# MISC.net
KiCad netlist of a schematic drawn in Altium Designer
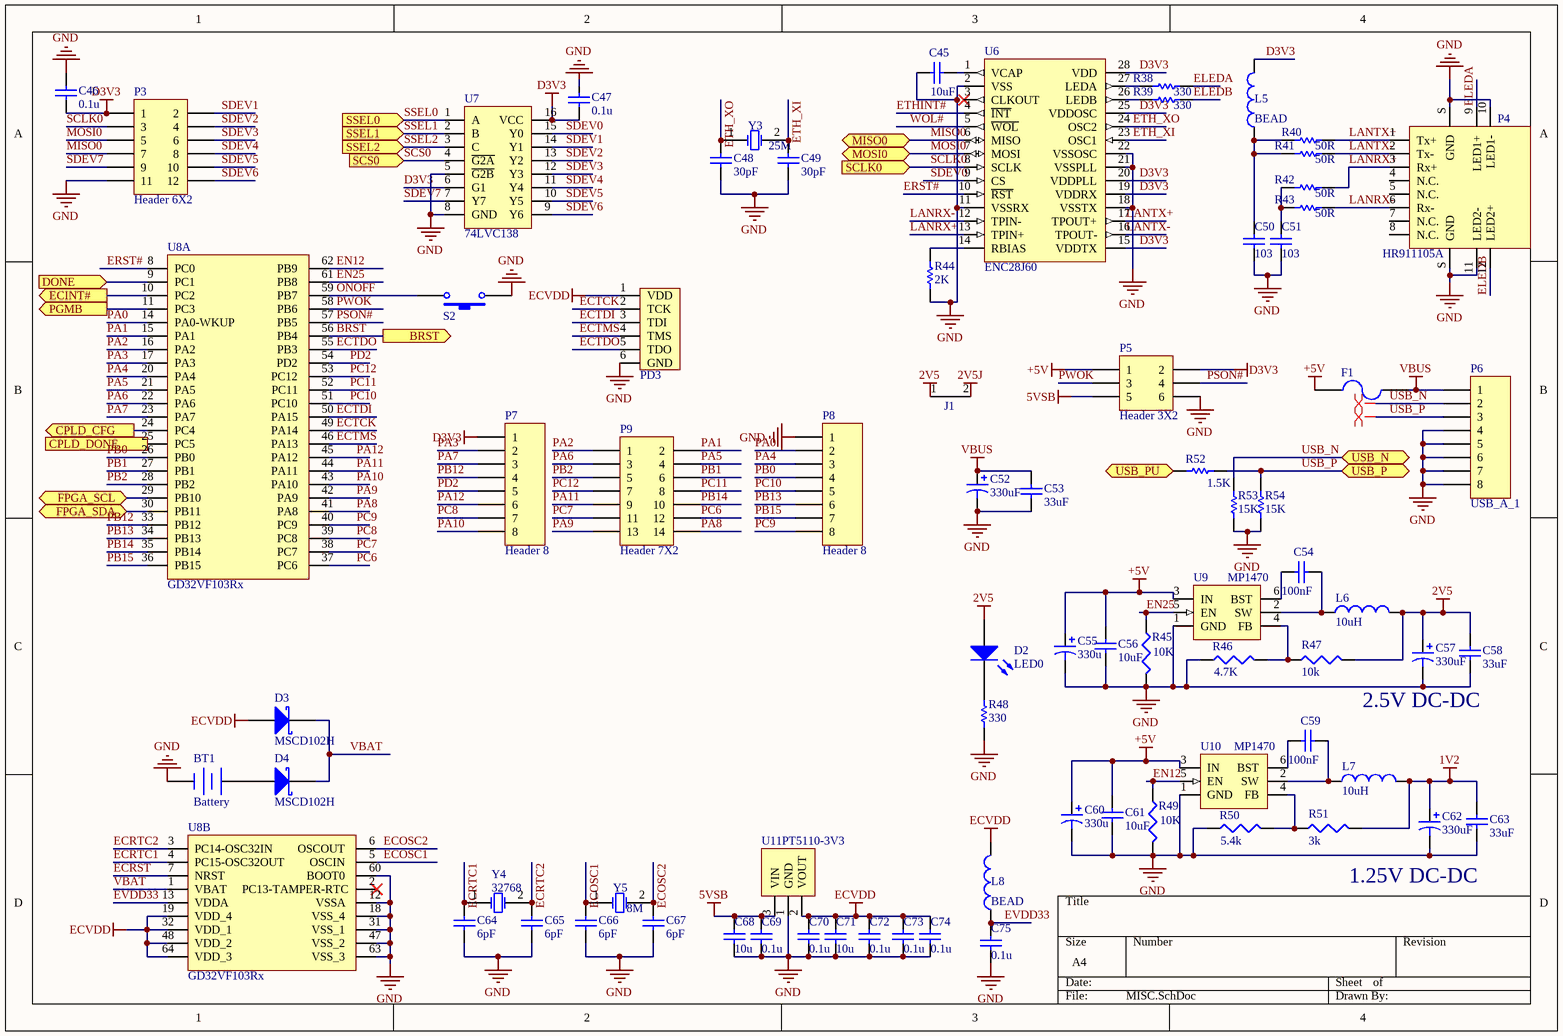
[diagram p0: MISC.SchDoc]

(export (version "E")
  (design (tool "Eeschema 10.0.6"))
  (components
    (comp (ref "BT1")
      (value "Battery")
      (footprint "BAT-CR1220")
      (description "Multicell Battery")
      (fields (field (name "PUBLISHER") "Altium Limited"))
      (libsource (lib "Miscellaneous Devices") (part "Battery"))
    )
    (comp (ref "C45")
      (value "10uF")
      (footprint "0603C")
      (description "Capacitor")
      (fields (field (name "Comment") "Cap") (field (name "PUBLISHER") "Altium Limited"))
      (libsource (lib "Miscellaneous Devices") (part "Cap"))
    )
    (comp (ref "C46")
      (value "0.1u")
      (footprint "0603C")
      (description "Capacitor")
      (fields (field (name "Comment") "Cap") (field (name "PUBLISHER") "Altium Limited"))
      (libsource (lib "Miscellaneous Devices") (part "Cap"))
    )
    (comp (ref "C47")
      (value "0.1u")
      (footprint "0603C")
      (description "Capacitor")
      (fields (field (name "Comment") "Cap") (field (name "PUBLISHER") "Altium Limited"))
      (libsource (lib "Miscellaneous Devices") (part "Cap"))
    )
    (comp (ref "C48")
      (value "30pF")
      (footprint "0603C")
      (description "Capacitor")
      (fields (field (name "Comment") "Cap") (field (name "PUBLISHER") "Altium Limited"))
      (libsource (lib "Miscellaneous Devices") (part "Cap"))
    )
    (comp (ref "C49")
      (value "30pF")
      (footprint "0603C")
      (description "Capacitor")
      (fields (field (name "Comment") "Cap") (field (name "PUBLISHER") "Altium Limited"))
      (libsource (lib "Miscellaneous Devices") (part "Cap"))
    )
    (comp (ref "C50")
      (value "103")
      (footprint "0603C")
      (description "Capacitor")
      (fields (field (name "Comment") "Cap") (field (name "PUBLISHER") "Altium Limited"))
      (libsource (lib "Miscellaneous Devices") (part "Cap"))
    )
    (comp (ref "C51")
      (value "103")
      (footprint "0603C")
      (description "Capacitor")
      (fields (field (name "Comment") "Cap") (field (name "PUBLISHER") "Altium Limited"))
      (libsource (lib "Miscellaneous Devices") (part "Cap"))
    )
    (comp (ref "C52")
      (value "330uF")
      (footprint "TanCap-1210")
      (description "Polarized Capacitor (Radial)")
      (fields (field (name "Comment") "330u") (field (name "PUBLISHER") "Altium Limited"))
      (libsource (lib "Miscellaneous Devices") (part "Cap Pol1"))
    )
    (comp (ref "C53")
      (value "33uF")
      (footprint "0603C")
      (description "Ceramic Capacitor 0603")
      (fields (field (name "Comment") "106") (field (name "PUBLISHER") "Altium Limited"))
      (libsource (lib "Miscellaneous Devices") (part "Cap"))
    )
    (comp (ref "C54")
      (value "100nF")
      (footprint "0603C")
      (description "Ceramic Capacitor 0603")
      (fields (field (name "Comment") "104") (field (name "PUBLISHER") "Altium Limited"))
      (libsource (lib "Miscellaneous Devices") (part "Cap"))
    )
    (comp (ref "C55")
      (value "330u")
      (footprint "TanCap-1210")
      (description "Polarized Capacitor (Radial)")
      (fields (field (name "PUBLISHER") "Altium Limited"))
      (libsource (lib "Miscellaneous Devices") (part "Cap Pol1"))
    )
    (comp (ref "C56")
      (value "10uF")
      (footprint "0603C")
      (description "Ceramic Capacitor 0603")
      (fields (field (name "Comment") "106") (field (name "PUBLISHER") "Altium Limited"))
      (libsource (lib "Miscellaneous Devices") (part "Cap"))
    )
    (comp (ref "C57")
      (value "330uF")
      (footprint "TanCap-1210")
      (description "Polarized Capacitor (Radial)")
      (fields (field (name "Comment") "330u") (field (name "PUBLISHER") "Altium Limited"))
      (libsource (lib "Miscellaneous Devices") (part "Cap Pol1"))
    )
    (comp (ref "C58")
      (value "33uF")
      (footprint "0603C")
      (description "Ceramic Capacitor 0603")
      (fields (field (name "Comment") "106") (field (name "PUBLISHER") "Altium Limited"))
      (libsource (lib "Miscellaneous Devices") (part "Cap"))
    )
    (comp (ref "C59")
      (value "100nF")
      (footprint "0603C")
      (description "Ceramic Capacitor 0603")
      (fields (field (name "Comment") "104") (field (name "PUBLISHER") "Altium Limited"))
      (libsource (lib "Miscellaneous Devices") (part "Cap"))
    )
    (comp (ref "C60")
      (value "330u")
      (footprint "TanCap-1210")
      (description "Polarized Capacitor (Radial)")
      (fields (field (name "PUBLISHER") "Altium Limited"))
      (libsource (lib "Miscellaneous Devices") (part "Cap Pol1"))
    )
    (comp (ref "C61")
      (value "10uF")
      (footprint "0603C")
      (description "Ceramic Capacitor 0603")
      (fields (field (name "Comment") "106") (field (name "PUBLISHER") "Altium Limited"))
      (libsource (lib "Miscellaneous Devices") (part "Cap"))
    )
    (comp (ref "C62")
      (value "330uF")
      (footprint "TanCap-1210")
      (description "Polarized Capacitor (Radial)")
      (fields (field (name "Comment") "330u") (field (name "PUBLISHER") "Altium Limited"))
      (libsource (lib "Miscellaneous Devices") (part "Cap Pol1"))
    )
    (comp (ref "C63")
      (value "33uF")
      (footprint "0603C")
      (description "Ceramic Capacitor 0603")
      (fields (field (name "Comment") "106") (field (name "PUBLISHER") "Altium Limited"))
      (libsource (lib "Miscellaneous Devices") (part "Cap"))
    )
    (comp (ref "C64")
      (value "6pF")
      (footprint "0603C")
      (description "Capacitor")
      (fields (field (name "Comment") "Cap") (field (name "PUBLISHER") "Altium Limited"))
      (libsource (lib "Miscellaneous Devices") (part "Cap"))
    )
    (comp (ref "C65")
      (value "6pF")
      (footprint "0603C")
      (description "Capacitor")
      (fields (field (name "Comment") "Cap") (field (name "PUBLISHER") "Altium Limited"))
      (libsource (lib "Miscellaneous Devices") (part "Cap"))
    )
    (comp (ref "C66")
      (value "6pF")
      (footprint "0603C")
      (description "Capacitor")
      (fields (field (name "Comment") "Cap") (field (name "PUBLISHER") "Altium Limited"))
      (libsource (lib "Miscellaneous Devices") (part "Cap"))
    )
    (comp (ref "C67")
      (value "6pF")
      (footprint "0603C")
      (description "Capacitor")
      (fields (field (name "Comment") "Cap") (field (name "PUBLISHER") "Altium Limited"))
      (libsource (lib "Miscellaneous Devices") (part "Cap"))
    )
    (comp (ref "C68")
      (value "10u")
      (footprint "0603C")
      (description "Capacitor")
      (fields (field (name "Comment") "Cap") (field (name "PUBLISHER") "Altium Limited"))
      (libsource (lib "Miscellaneous Devices") (part "Cap"))
    )
    (comp (ref "C69")
      (value "0.1u")
      (footprint "0603C")
      (description "Capacitor")
      (fields (field (name "Comment") "Cap") (field (name "PUBLISHER") "Altium Limited"))
      (libsource (lib "Miscellaneous Devices") (part "Cap"))
    )
    (comp (ref "C70")
      (value "0.1u")
      (footprint "0603C")
      (description "Capacitor")
      (fields (field (name "Comment") "Cap") (field (name "PUBLISHER") "Altium Limited"))
      (libsource (lib "Miscellaneous Devices") (part "Cap"))
    )
    (comp (ref "C71")
      (value "10u")
      (footprint "0603C")
      (description "Capacitor")
      (fields (field (name "Comment") "Cap") (field (name "PUBLISHER") "Altium Limited"))
      (libsource (lib "Miscellaneous Devices") (part "Cap"))
    )
    (comp (ref "C72")
      (value "0.1u")
      (footprint "0603C")
      (description "Capacitor")
      (fields (field (name "Comment") "Cap") (field (name "PUBLISHER") "Altium Limited"))
      (libsource (lib "Miscellaneous Devices") (part "Cap"))
    )
    (comp (ref "C73")
      (value "0.1u")
      (footprint "0603C")
      (description "Capacitor")
      (fields (field (name "Comment") "Cap") (field (name "PUBLISHER") "Altium Limited"))
      (libsource (lib "Miscellaneous Devices") (part "Cap"))
    )
    (comp (ref "C74")
      (value "0.1u")
      (footprint "0603C")
      (description "Capacitor")
      (fields (field (name "Comment") "Cap") (field (name "PUBLISHER") "Altium Limited"))
      (libsource (lib "Miscellaneous Devices") (part "Cap"))
    )
    (comp (ref "C75")
      (value "0.1u")
      (footprint "0603C")
      (description "Capacitor")
      (fields (field (name "Comment") "Cap") (field (name "PUBLISHER") "Altium Limited"))
      (libsource (lib "Miscellaneous Devices") (part "Cap"))
    )
    (comp (ref "D2")
      (value "LED0")
      (footprint "0805LED1")
      (description "Typical INFRARED GaAs LED")
      (fields (field (name "PUBLISHER") "Altium Limited"))
      (libsource (lib "Miscellaneous Devices") (part "LED0"))
    )
    (comp (ref "D3")
      (value "MSCD102H")
      (footprint "0805LED2")
      (description "Schottky Diode")
      (fields (field (name "PUBLISHER") "Altium Limited"))
      (libsource (lib "Miscellaneous Devices") (part "D Schottky"))
    )
    (comp (ref "D4")
      (value "MSCD102H")
      (footprint "0805LED2")
      (description "Schottky Diode")
      (fields (field (name "PUBLISHER") "Altium Limited"))
      (libsource (lib "Miscellaneous Devices") (part "D Schottky"))
    )
    (comp (ref "F1")
      (value "Fuse 2")
      (footprint "Fusebux_5x20")
      (description "Fuse")
      (fields (field (name "PUBLISHER") "Altium Limited"))
      (libsource (lib "Miscellaneous Devices") (part "Fuse 2"))
    )
    (comp (ref "J1")
      (value "Jumper")
      (footprint "Jumper 10mm")
      (libsource (lib "RV_AT_Ports") (part "Jumper"))
    )
    (comp (ref "L5")
      (value "BEAD")
      (footprint "0603C")
      (description "Inductor")
      (fields (field (name "PUBLISHER") "Altium Limited"))
      (libsource (lib "Miscellaneous Devices") (part "Inductor"))
    )
    (comp (ref "L6")
      (value "10uH")
      (footprint "PIND0650")
      (description "Inductor 0606")
      (fields (field (name "PUBLISHER") "Altium Limited"))
      (libsource (lib "Miscellaneous Devices") (part "Inductor"))
    )
    (comp (ref "L7")
      (value "10uH")
      (footprint "PIND0650")
      (description "Inductor 0606")
      (fields (field (name "PUBLISHER") "Altium Limited"))
      (libsource (lib "Miscellaneous Devices") (part "Inductor"))
    )
    (comp (ref "L8")
      (value "BEAD")
      (footprint "0603C")
      (description "Inductor")
      (fields (field (name "PUBLISHER") "Altium Limited"))
      (libsource (lib "Miscellaneous Devices") (part "Inductor"))
    )
    (comp (ref "P3")
      (value "Header 6X2")
      (footprint "HDR2X6")
      (description "Header, 6-Pin, Dual row")
      (fields (field (name "PUBLISHER") "Altium Limited"))
      (libsource (lib "Miscellaneous Connectors") (part "Header 6X2"))
    )
    (comp (ref "P4")
      (value "HR911105A")
      (footprint "HR911105A")
      (libsource (lib "ETH_Solution") (part "HR911105A"))
    )
    (comp (ref "P5")
      (value "Header 3X2")
      (footprint "PWRCONN-6P")
      (description "Header, 3-Pin, Dual row")
      (fields (field (name "PUBLISHER") "Altium Limited"))
      (libsource (lib "Miscellaneous Connectors") (part "Header 3X2"))
    )
    (comp (ref "P6")
      (value "USB_A_1")
      (footprint "USB-A_1")
      (description "Header, 8-Pin")
      (fields (field (name "PUBLISHER") "Altium Limited"))
      (libsource (lib "Miscellaneous Connectors") (part "Header 8"))
    )
    (comp (ref "P7")
      (value "Header 8")
      (footprint "HDR1X8")
      (description "Header, 8-Pin")
      (fields (field (name "PUBLISHER") "Altium Limited"))
      (libsource (lib "Miscellaneous Connectors") (part "Header 8"))
    )
    (comp (ref "P8")
      (value "Header 8")
      (footprint "HDR1X8")
      (description "Header, 8-Pin")
      (fields (field (name "PUBLISHER") "Altium Limited"))
      (libsource (lib "Miscellaneous Connectors") (part "Header 8"))
    )
    (comp (ref "P9")
      (value "Header 7X2")
      (footprint "HDR2X7_U")
      (description "Header, 7-Pin, Dual row")
      (fields (field (name "PUBLISHER") "Altium Limited"))
      (libsource (lib "Miscellaneous Connectors") (part "Header 7X2"))
    )
    (comp (ref "PD3") (value "JTAG") (footprint "DBGP7") (libsource (lib "RV_AT_Ports") (part "JTAG")))
    (comp (ref "R38")
      (value "330")
      (footprint "0603R")
      (description "Resistor")
      (fields (field (name "Comment") "Res1") (field (name "PUBLISHER") "Altium Limited"))
      (libsource (lib "Miscellaneous Devices") (part "Res1"))
    )
    (comp (ref "R39")
      (value "330")
      (footprint "0603R")
      (description "Resistor")
      (fields (field (name "Comment") "Res1") (field (name "PUBLISHER") "Altium Limited"))
      (libsource (lib "Miscellaneous Devices") (part "Res1"))
    )
    (comp (ref "R40")
      (value "50R")
      (footprint "0603R")
      (description "Resistor")
      (fields (field (name "Comment") "Res1") (field (name "PUBLISHER") "Altium Limited"))
      (libsource (lib "Miscellaneous Devices") (part "Res1"))
    )
    (comp (ref "R41")
      (value "50R")
      (footprint "0603R")
      (description "Resistor")
      (fields (field (name "Comment") "Res1") (field (name "PUBLISHER") "Altium Limited"))
      (libsource (lib "Miscellaneous Devices") (part "Res1"))
    )
    (comp (ref "R42")
      (value "50R")
      (footprint "0603R")
      (description "Resistor")
      (fields (field (name "Comment") "Res1") (field (name "PUBLISHER") "Altium Limited"))
      (libsource (lib "Miscellaneous Devices") (part "Res1"))
    )
    (comp (ref "R43")
      (value "50R")
      (footprint "0603R")
      (description "Resistor")
      (fields (field (name "Comment") "Res1") (field (name "PUBLISHER") "Altium Limited"))
      (libsource (lib "Miscellaneous Devices") (part "Res1"))
    )
    (comp (ref "R44")
      (value "2K")
      (footprint "0603R")
      (description "Resistor")
      (fields (field (name "Comment") "Res1") (field (name "PUBLISHER") "Altium Limited"))
      (libsource (lib "Miscellaneous Devices") (part "Res1"))
    )
    (comp (ref "R45")
      (value "10K")
      (footprint "0603R")
      (description "Resistor")
      (fields (field (name "PUBLISHER") "Altium Limited"))
      (libsource (lib "Miscellaneous Devices") (part "Res3"))
    )
    (comp (ref "R46")
      (value "4.7K")
      (footprint "0603R")
      (description "Resistor")
      (fields (field (name "Comment") "3K2") (field (name "PUBLISHER") "Altium Limited"))
      (libsource (lib "Miscellaneous Devices") (part "Res3"))
    )
    (comp (ref "R47")
      (value "10k")
      (footprint "0603R")
      (description "Resistor")
      (fields (field (name "Comment") "10K") (field (name "PUBLISHER") "Altium Limited"))
      (libsource (lib "Miscellaneous Devices") (part "Res3"))
    )
    (comp (ref "R48")
      (value "330")
      (footprint "0603R")
      (description "Resistor")
      (fields (field (name "Comment") "Res1") (field (name "PUBLISHER") "Altium Limited"))
      (libsource (lib "Miscellaneous Devices") (part "Res1"))
    )
    (comp (ref "R49")
      (value "10K")
      (footprint "0603R")
      (description "Resistor")
      (fields (field (name "PUBLISHER") "Altium Limited"))
      (libsource (lib "Miscellaneous Devices") (part "Res3"))
    )
    (comp (ref "R50")
      (value "5.4k")
      (footprint "0603R")
      (description "Resistor")
      (fields (field (name "Comment") "3K2") (field (name "PUBLISHER") "Altium Limited"))
      (libsource (lib "Miscellaneous Devices") (part "Res3"))
    )
    (comp (ref "R51")
      (value "3k")
      (footprint "0603R")
      (description "Resistor")
      (fields (field (name "Comment") "10K") (field (name "PUBLISHER") "Altium Limited"))
      (libsource (lib "Miscellaneous Devices") (part "Res3"))
    )
    (comp (ref "R52")
      (value "1.5K")
      (footprint "0603R")
      (description "Resistor")
      (fields (field (name "Comment") "Res1") (field (name "PUBLISHER") "Altium Limited"))
      (libsource (lib "Miscellaneous Devices") (part "Res1"))
    )
    (comp (ref "R53")
      (value "15K")
      (footprint "0603R")
      (description "Resistor")
      (fields (field (name "Comment") "Res1") (field (name "PUBLISHER") "Altium Limited"))
      (libsource (lib "Miscellaneous Devices") (part "Res1"))
    )
    (comp (ref "R54")
      (value "15K")
      (footprint "0603R")
      (description "Resistor")
      (fields (field (name "Comment") "Res1") (field (name "PUBLISHER") "Altium Limited"))
      (libsource (lib "Miscellaneous Devices") (part "Res1"))
    )
    (comp (ref "S2")
      (value "SW-PB")
      (footprint "Switch_SMT-022S-H2.5")
      (description "Switch")
      (fields (field (name "PUBLISHER") "Altium Limited"))
      (libsource (lib "Miscellaneous Devices") (part "SW-PB"))
    )
    (comp (ref "U6")
      (value "ENC28J60")
      (footprint "SOIC28P1040X265")
      (libsource (lib "ETH_Solution") (part "ENC28J60"))
    )
    (comp (ref "U7") (value "74LVC138") (footprint "SO-16") (libsource (lib "74xLogic") (part "74x138")))
    (comp (ref "U8")
      (value "GD32VF103Rx")
      (footprint "AD格式PCB库:QFP12X12-64(N)")
      (libsource (lib "32bMCU") (part "GD32VF103Rx"))
    )
    (comp (ref "U9")
      (value "MP1470")
      (footprint "SOT95P245X110-6N")
      (libsource (lib "PowerChips") (part "MP1470"))
    )
    (comp (ref "U10")
      (value "MP1470")
      (footprint "SOT95P245X110-6N")
      (libsource (lib "PowerChips") (part "MP1470"))
    )
    (comp (ref "U11")
      (value "PT5110-3V3")
      (footprint "SOT323-N")
      (libsource (lib "PowerChips") (part "PT5110"))
    )
    (comp (ref "Y3")
      (value "25M")
      (footprint "XTAL-5032")
      (description "Crystal Oscillator")
      (fields (field (name "PUBLISHER") "Altium Limited"))
      (libsource (lib "Miscellaneous Devices") (part "XTAL"))
    )
    (comp (ref "Y4")
      (value "32768")
      (footprint "PublicPCBLib:XTAL-3215")
      (description "Crystal Oscillator")
      (fields (field (name "PUBLISHER") "Altium Limited"))
      (libsource (lib "Miscellaneous Devices") (part "XTAL"))
    )
    (comp (ref "Y5")
      (value "8M")
      (footprint "XTAL-5032")
      (description "Crystal Oscillator")
      (fields (field (name "PUBLISHER") "Altium Limited"))
      (libsource (lib "Miscellaneous Devices") (part "XTAL"))
    )
  )
  (nets
    (net (code "1") (name "+5V") (class "Default")
      (node (ref "C55") (pin "1") (pinfunction "1_1") (pintype "passive"))
      (node (ref "C56") (pin "2") (pinfunction "2_2") (pintype "passive"))
      (node (ref "C60") (pin "1") (pinfunction "1_1") (pintype "passive"))
      (node (ref "C61") (pin "2") (pinfunction "2_2") (pintype "passive"))
      (node (ref "F1") (pin "1") (pinfunction "1_1") (pintype "passive"))
      (node (ref "P5") (pin "1") (pinfunction "1_1") (pintype "passive"))
      (node (ref "U10") (pin "3") (pinfunction "IN_3") (pintype "power_in"))
      (node (ref "U9") (pin "3") (pinfunction "IN_3") (pintype "power_in"))
    )
    (net (code "2") (name "/BRST") (class "Default")
      (node (ref "U8") (pin "56") (pinfunction "PB4_56") (pintype "passive"))
    )
    (net (code "3") (name "/CPLD_CFG") (class "Default")
      (node (ref "U8") (pin "24") (pinfunction "PC4_24") (pintype "passive"))
    )
    (net (code "4") (name "/CPLD_DONE") (class "Default")
      (node (ref "U8") (pin "25") (pinfunction "PC5_25") (pintype "passive"))
    )
    (net (code "5") (name "/DONE") (class "Default")
      (node (ref "U8") (pin "9") (pinfunction "PC1_9") (pintype "passive"))
    )
    (net (code "6") (name "/ECINT#") (class "Default")
      (node (ref "U8") (pin "10") (pinfunction "PC2_10") (pintype "passive"))
    )
    (net (code "7") (name "/ECOSC1") (class "Default")
      (node (ref "C66") (pin "1") (pinfunction "1_1") (pintype "passive"))
      (node (ref "U8") (pin "5") (pinfunction "OSCIN_5") (pintype "passive"))
      (node (ref "Y5") (pin "1") (pinfunction "OSC1_1") (pintype "passive"))
    )
    (net (code "8") (name "/ECOSC2") (class "Default")
      (node (ref "C67") (pin "1") (pinfunction "1_1") (pintype "passive"))
      (node (ref "U8") (pin "6") (pinfunction "OSCOUT_6") (pintype "passive"))
      (node (ref "Y5") (pin "2") (pinfunction "OSC2_2") (pintype "passive"))
    )
    (net (code "9") (name "/ECRST") (class "Default")
      (node (ref "U8") (pin "7") (pinfunction "NRST_7") (pintype "passive"))
    )
    (net (code "10") (name "/ECRTC1") (class "Default")
      (node (ref "C64") (pin "1") (pinfunction "1_1") (pintype "passive"))
      (node (ref "U8") (pin "4") (pinfunction "PC15-OSC32OUT_4") (pintype "passive"))
      (node (ref "Y4") (pin "1") (pinfunction "OSC1_1") (pintype "passive"))
    )
    (net (code "11") (name "/ECRTC2") (class "Default")
      (node (ref "C65") (pin "1") (pinfunction "1_1") (pintype "passive"))
      (node (ref "U8") (pin "3") (pinfunction "PC14-OSC32IN_3") (pintype "passive"))
      (node (ref "Y4") (pin "2") (pinfunction "OSC2_2") (pintype "passive"))
    )
    (net (code "12") (name "/ECTCK") (class "Default")
      (node (ref "PD3") (pin "2") (pinfunction "TCK_2") (pintype "passive"))
      (node (ref "U8") (pin "49") (pinfunction "PA14_49") (pintype "passive"))
    )
    (net (code "13") (name "/ECTDI") (class "Default")
      (node (ref "PD3") (pin "3") (pinfunction "TDI_3") (pintype "passive"))
      (node (ref "U8") (pin "50") (pinfunction "PA15_50") (pintype "passive"))
    )
    (net (code "14") (name "/ECTDO") (class "Default")
      (node (ref "PD3") (pin "5") (pinfunction "TDO_5") (pintype "passive"))
      (node (ref "U8") (pin "55") (pinfunction "PB3_55") (pintype "passive"))
    )
    (net (code "15") (name "/ECTMS") (class "Default")
      (node (ref "PD3") (pin "4") (pinfunction "TMS_4") (pintype "passive"))
      (node (ref "U8") (pin "46") (pinfunction "PA13_46") (pintype "passive"))
    )
    (net (code "16") (name "/ELEDA") (class "Default")
      (node (ref "P4") (pin "9") (pinfunction "LED1+_9") (pintype "passive"))
      (node (ref "R38") (pin "1") (pinfunction "1_1") (pintype "passive"))
    )
    (net (code "17") (name "/ELEDB") (class "Default")
      (node (ref "P4") (pin "12") (pinfunction "LED2+_12") (pintype "passive"))
      (node (ref "R39") (pin "1") (pinfunction "1_1") (pintype "passive"))
    )
    (net (code "18") (name "/EN12") (class "Default")
      (node (ref "R49") (pin "1") (pinfunction "1_1") (pintype "passive"))
      (node (ref "U10") (pin "5") (pinfunction "EN_5") (pintype "input"))
      (node (ref "U8") (pin "62") (pinfunction "PB9_62") (pintype "passive"))
    )
    (net (code "19") (name "/EN25") (class "Default")
      (node (ref "R45") (pin "1") (pinfunction "1_1") (pintype "passive"))
      (node (ref "U8") (pin "61") (pinfunction "PB8_61") (pintype "passive"))
      (node (ref "U9") (pin "5") (pinfunction "EN_5") (pintype "input"))
    )
    (net (code "20") (name "/ERST#") (class "Default")
      (node (ref "U6") (pin "10") (pinfunction "~{RST}_10") (pintype "input"))
      (node (ref "U8") (pin "8") (pinfunction "PC0_8") (pintype "passive"))
    )
    (net (code "21") (name "/ETHINT#") (class "Default")
      (node (ref "U6") (pin "4") (pinfunction "~{INT}_4") (pintype "output"))
    )
    (net (code "22") (name "/ETH_XI") (class "Default")
      (node (ref "C49") (pin "1") (pinfunction "1_1") (pintype "passive"))
      (node (ref "U6") (pin "23") (pinfunction "OSC1_23") (pintype "input"))
      (node (ref "Y3") (pin "2") (pinfunction "OSC2_2") (pintype "passive"))
    )
    (net (code "23") (name "/ETH_XO") (class "Default")
      (node (ref "C48") (pin "1") (pinfunction "1_1") (pintype "passive"))
      (node (ref "U6") (pin "24") (pinfunction "OSC2_24") (pintype "output"))
      (node (ref "Y3") (pin "1") (pinfunction "OSC1_1") (pintype "passive"))
    )
    (net (code "24") (name "/EVDD33") (class "Default")
      (node (ref "C75") (pin "2") (pinfunction "2_2") (pintype "passive"))
      (node (ref "L8") (pin "1") (pinfunction "1_1") (pintype "passive"))
      (node (ref "U8") (pin "13") (pinfunction "VDDA_13") (pintype "passive"))
    )
    (net (code "25") (name "/FPGA_SCL") (class "Default")
      (node (ref "U8") (pin "29") (pinfunction "PB10_29") (pintype "passive"))
    )
    (net (code "26") (name "/FPGA_SDA") (class "Default")
      (node (ref "U8") (pin "30") (pinfunction "PB11_30") (pintype "passive"))
    )
    (net (code "27") (name "/LANRX+") (class "Default")
      (node (ref "P4") (pin "3") (pinfunction "Rx+_3") (pintype "passive"))
      (node (ref "R42") (pin "1") (pinfunction "1_1") (pintype "passive"))
      (node (ref "U6") (pin "13") (pinfunction "TPIN+_13") (pintype "input"))
    )
    (net (code "28") (name "/LANRX-") (class "Default")
      (node (ref "P4") (pin "6") (pinfunction "Rx-_6") (pintype "passive"))
      (node (ref "R43") (pin "1") (pinfunction "1_1") (pintype "passive"))
      (node (ref "U6") (pin "12") (pinfunction "TPIN-_12") (pintype "input"))
    )
    (net (code "29") (name "/LANTX+") (class "Default")
      (node (ref "P4") (pin "1") (pinfunction "Tx+_1") (pintype "passive"))
      (node (ref "R40") (pin "1") (pinfunction "1_1") (pintype "passive"))
      (node (ref "U6") (pin "17") (pinfunction "TPOUT+_17") (pintype "output"))
    )
    (net (code "30") (name "/LANTX-") (class "Default")
      (node (ref "P4") (pin "2") (pinfunction "Tx-_2") (pintype "passive"))
      (node (ref "R41") (pin "1") (pinfunction "1_1") (pintype "passive"))
      (node (ref "U6") (pin "16") (pinfunction "TPOUT-_16") (pintype "output"))
    )
    (net (code "31") (name "/MISO0") (class "Default")
      (node (ref "P3") (pin "7") (pinfunction "7_7") (pintype "passive"))
      (node (ref "U6") (pin "6") (pinfunction "MISO_6") (pintype "bidirectional"))
    )
    (net (code "32") (name "/MOSI0") (class "Default")
      (node (ref "P3") (pin "5") (pinfunction "5_5") (pintype "passive"))
      (node (ref "U6") (pin "7") (pinfunction "MOSI_7") (pintype "bidirectional"))
    )
    (net (code "33") (name "/ONOFF") (class "Default")
      (node (ref "S2") (pin "2") (pinfunction "2_2") (pintype "passive"))
      (node (ref "U8") (pin "59") (pinfunction "PB7_59") (pintype "passive"))
    )
    (net (code "34") (name "/PA0") (class "Default")
      (node (ref "P8") (pin "2") (pinfunction "2_2") (pintype "passive"))
      (node (ref "U8") (pin "14") (pinfunction "PA0-WKUP_14") (pintype "passive"))
    )
    (net (code "35") (name "/PA1") (class "Default")
      (node (ref "P9") (pin "2") (pinfunction "2_2") (pintype "passive"))
      (node (ref "U8") (pin "15") (pinfunction "PA1_15") (pintype "passive"))
    )
    (net (code "36") (name "/PA2") (class "Default")
      (node (ref "P9") (pin "1") (pinfunction "1_1") (pintype "passive"))
      (node (ref "U8") (pin "16") (pinfunction "PA2_16") (pintype "passive"))
    )
    (net (code "37") (name "/PA3") (class "Default")
      (node (ref "P7") (pin "2") (pinfunction "2_2") (pintype "passive"))
      (node (ref "U8") (pin "17") (pinfunction "PA3_17") (pintype "passive"))
    )
    (net (code "38") (name "/PA4") (class "Default")
      (node (ref "P8") (pin "3") (pinfunction "3_3") (pintype "passive"))
      (node (ref "U8") (pin "20") (pinfunction "PA4_20") (pintype "passive"))
    )
    (net (code "39") (name "/PA5") (class "Default")
      (node (ref "P9") (pin "4") (pinfunction "4_4") (pintype "passive"))
      (node (ref "U8") (pin "21") (pinfunction "PA5_21") (pintype "passive"))
    )
    (net (code "40") (name "/PA6") (class "Default")
      (node (ref "P9") (pin "3") (pinfunction "3_3") (pintype "passive"))
      (node (ref "U8") (pin "22") (pinfunction "PA6_22") (pintype "passive"))
    )
    (net (code "41") (name "/PA7") (class "Default")
      (node (ref "P7") (pin "3") (pinfunction "3_3") (pintype "passive"))
      (node (ref "U8") (pin "23") (pinfunction "PA7_23") (pintype "passive"))
    )
    (net (code "42") (name "/PA8") (class "Default")
      (node (ref "P9") (pin "14") (pinfunction "14_14") (pintype "passive"))
      (node (ref "U8") (pin "41") (pinfunction "PA8_41") (pintype "passive"))
    )
    (net (code "43") (name "/PA9") (class "Default")
      (node (ref "P9") (pin "13") (pinfunction "13_13") (pintype "passive"))
      (node (ref "U8") (pin "42") (pinfunction "PA9_42") (pintype "passive"))
    )
    (net (code "44") (name "/PA10") (class "Default")
      (node (ref "P7") (pin "8") (pinfunction "8_8") (pintype "passive"))
      (node (ref "U8") (pin "43") (pinfunction "PA10_43") (pintype "passive"))
    )
    (net (code "45") (name "/PA11") (class "Default")
      (node (ref "P9") (pin "9") (pinfunction "9_9") (pintype "passive"))
      (node (ref "U8") (pin "44") (pinfunction "PA11_44") (pintype "passive"))
    )
    (net (code "46") (name "/PA12") (class "Default")
      (node (ref "P7") (pin "6") (pinfunction "6_6") (pintype "passive"))
      (node (ref "U8") (pin "45") (pinfunction "PA12_45") (pintype "passive"))
    )
    (net (code "47") (name "/PB0") (class "Default")
      (node (ref "P8") (pin "4") (pinfunction "4_4") (pintype "passive"))
      (node (ref "U8") (pin "26") (pinfunction "PB0_26") (pintype "passive"))
    )
    (net (code "48") (name "/PB1") (class "Default")
      (node (ref "P9") (pin "6") (pinfunction "6_6") (pintype "passive"))
      (node (ref "U8") (pin "27") (pinfunction "PB1_27") (pintype "passive"))
    )
    (net (code "49") (name "/PB2") (class "Default")
      (node (ref "P9") (pin "5") (pinfunction "5_5") (pintype "passive"))
      (node (ref "U8") (pin "28") (pinfunction "PB2_28") (pintype "passive"))
    )
    (net (code "50") (name "/PB12") (class "Default")
      (node (ref "P7") (pin "4") (pinfunction "4_4") (pintype "passive"))
      (node (ref "U8") (pin "33") (pinfunction "PB12_33") (pintype "passive"))
    )
    (net (code "51") (name "/PB13") (class "Default")
      (node (ref "P8") (pin "6") (pinfunction "6_6") (pintype "passive"))
      (node (ref "U8") (pin "34") (pinfunction "PB13_34") (pintype "passive"))
    )
    (net (code "52") (name "/PB14") (class "Default")
      (node (ref "P9") (pin "10") (pinfunction "10_10") (pintype "passive"))
      (node (ref "U8") (pin "35") (pinfunction "PB14_35") (pintype "passive"))
    )
    (net (code "53") (name "/PB15") (class "Default")
      (node (ref "P8") (pin "7") (pinfunction "7_7") (pintype "passive"))
      (node (ref "U8") (pin "36") (pinfunction "PB15_36") (pintype "passive"))
    )
    (net (code "54") (name "/PC6") (class "Default")
      (node (ref "P9") (pin "12") (pinfunction "12_12") (pintype "passive"))
      (node (ref "U8") (pin "37") (pinfunction "PC6_37") (pintype "passive"))
    )
    (net (code "55") (name "/PC7") (class "Default")
      (node (ref "P9") (pin "11") (pinfunction "11_11") (pintype "passive"))
      (node (ref "U8") (pin "38") (pinfunction "PC7_38") (pintype "passive"))
    )
    (net (code "56") (name "/PC8") (class "Default")
      (node (ref "P7") (pin "7") (pinfunction "7_7") (pintype "passive"))
      (node (ref "U8") (pin "39") (pinfunction "PC8_39") (pintype "passive"))
    )
    (net (code "57") (name "/PC9") (class "Default")
      (node (ref "P8") (pin "8") (pinfunction "8_8") (pintype "passive"))
      (node (ref "U8") (pin "40") (pinfunction "PC9_40") (pintype "passive"))
    )
    (net (code "58") (name "/PC10") (class "Default")
      (node (ref "P8") (pin "5") (pinfunction "5_5") (pintype "passive"))
      (node (ref "U8") (pin "51") (pinfunction "PC10_51") (pintype "passive"))
    )
    (net (code "59") (name "/PC11") (class "Default")
      (node (ref "P9") (pin "8") (pinfunction "8_8") (pintype "passive"))
      (node (ref "U8") (pin "52") (pinfunction "PC11_52") (pintype "passive"))
    )
    (net (code "60") (name "/PC12") (class "Default")
      (node (ref "P9") (pin "7") (pinfunction "7_7") (pintype "passive"))
      (node (ref "U8") (pin "53") (pinfunction "PC12_53") (pintype "passive"))
    )
    (net (code "61") (name "/PD2") (class "Default")
      (node (ref "P7") (pin "5") (pinfunction "5_5") (pintype "passive"))
      (node (ref "U8") (pin "54") (pinfunction "PD2_54") (pintype "passive"))
    )
    (net (code "62") (name "/PGMB") (class "Default")
      (node (ref "U8") (pin "11") (pinfunction "PC3_11") (pintype "passive"))
    )
    (net (code "63") (name "/PSON#") (class "Default")
      (node (ref "P5") (pin "4") (pinfunction "4_4") (pintype "passive"))
      (node (ref "U8") (pin "57") (pinfunction "PB5_57") (pintype "passive"))
    )
    (net (code "64") (name "/PWOK") (class "Default")
      (node (ref "P5") (pin "3") (pinfunction "3_3") (pintype "passive"))
      (node (ref "U8") (pin "58") (pinfunction "PB6_58") (pintype "passive"))
    )
    (net (code "65") (name "/SCLK0") (class "Default")
      (node (ref "P3") (pin "3") (pinfunction "3_3") (pintype "passive"))
      (node (ref "U6") (pin "8") (pinfunction "SCLK_8") (pintype "input"))
    )
    (net (code "66") (name "/SCS0") (class "Default")
      (node (ref "U7") (pin "4") (pinfunction "~{G2A}_4") (pintype "passive"))
    )
    (net (code "67") (name "/SDEV0") (class "Default")
      (node (ref "U6") (pin "9") (pinfunction "CS_9") (pintype "input"))
      (node (ref "U7") (pin "15") (pinfunction "Y0_15") (pintype "passive"))
    )
    (net (code "68") (name "/SDEV1") (class "Default")
      (node (ref "P3") (pin "2") (pinfunction "2_2") (pintype "passive"))
      (node (ref "U7") (pin "14") (pinfunction "Y1_14") (pintype "passive"))
    )
    (net (code "69") (name "/SDEV2") (class "Default")
      (node (ref "P3") (pin "4") (pinfunction "4_4") (pintype "passive"))
      (node (ref "U7") (pin "13") (pinfunction "Y2_13") (pintype "passive"))
    )
    (net (code "70") (name "/SDEV3") (class "Default")
      (node (ref "P3") (pin "6") (pinfunction "6_6") (pintype "passive"))
      (node (ref "U7") (pin "12") (pinfunction "Y3_12") (pintype "passive"))
    )
    (net (code "71") (name "/SDEV4") (class "Default")
      (node (ref "P3") (pin "8") (pinfunction "8_8") (pintype "passive"))
      (node (ref "U7") (pin "11") (pinfunction "Y4_11") (pintype "passive"))
    )
    (net (code "72") (name "/SDEV5") (class "Default")
      (node (ref "P3") (pin "10") (pinfunction "10_10") (pintype "passive"))
      (node (ref "U7") (pin "10") (pinfunction "Y5_10") (pintype "passive"))
    )
    (net (code "73") (name "/SDEV6") (class "Default")
      (node (ref "P3") (pin "12") (pinfunction "12_12") (pintype "passive"))
      (node (ref "U7") (pin "9") (pinfunction "Y6_9") (pintype "passive"))
    )
    (net (code "74") (name "/SDEV7") (class "Default")
      (node (ref "P3") (pin "9") (pinfunction "9_9") (pintype "passive"))
      (node (ref "U7") (pin "7") (pinfunction "Y7_7") (pintype "passive"))
    )
    (net (code "75") (name "/SSEL0") (class "Default")
      (node (ref "U7") (pin "1") (pinfunction "A_1") (pintype "passive"))
    )
    (net (code "76") (name "/SSEL1") (class "Default")
      (node (ref "U7") (pin "2") (pinfunction "B_2") (pintype "passive"))
    )
    (net (code "77") (name "/SSEL2") (class "Default")
      (node (ref "U7") (pin "3") (pinfunction "C_3") (pintype "passive"))
    )
    (net (code "78") (name "/USB_N") (class "Default")
      (node (ref "P6") (pin "2") (pinfunction "2_2") (pintype "passive"))
      (node (ref "R53") (pin "1") (pinfunction "1_1") (pintype "passive"))
    )
    (net (code "79") (name "/USB_P") (class "Default")
      (node (ref "P6") (pin "3") (pinfunction "3_3") (pintype "passive"))
      (node (ref "R52") (pin "2") (pinfunction "2_2") (pintype "passive"))
      (node (ref "R54") (pin "1") (pinfunction "1_1") (pintype "passive"))
    )
    (net (code "80") (name "/USB_PU") (class "Default")
      (node (ref "R52") (pin "1") (pinfunction "1_1") (pintype "passive"))
    )
    (net (code "81") (name "/VBAT") (class "Default")
      (node (ref "D3") (pin "2") (pinfunction "K_2") (pintype "passive"))
      (node (ref "D4") (pin "2") (pinfunction "K_2") (pintype "passive"))
      (node (ref "U8") (pin "1") (pinfunction "VBAT_1") (pintype "passive"))
    )
    (net (code "82") (name "/WOL#") (class "Default")
      (node (ref "U6") (pin "5") (pinfunction "~{WOL}_5") (pintype "output"))
    )
    (net (code "83") (name "1V2") (class "Default")
      (node (ref "C62") (pin "1") (pinfunction "1_1") (pintype "passive"))
      (node (ref "C63") (pin "2") (pinfunction "2_2") (pintype "passive"))
      (node (ref "L7") (pin "2") (pinfunction "2_2") (pintype "passive"))
      (node (ref "R51") (pin "2") (pinfunction "2_2") (pintype "passive"))
    )
    (net (code "84") (name "2V5") (class "Default")
      (node (ref "C57") (pin "1") (pinfunction "1_1") (pintype "passive"))
      (node (ref "C58") (pin "2") (pinfunction "2_2") (pintype "passive"))
      (node (ref "D2") (pin "1") (pinfunction "A_1") (pintype "passive"))
      (node (ref "J1") (pin "1") (pintype "passive"))
      (node (ref "L6") (pin "2") (pinfunction "2_2") (pintype "passive"))
      (node (ref "R47") (pin "2") (pinfunction "2_2") (pintype "passive"))
    )
    (net (code "85") (name "2V5J") (class "Default") (node (ref "J1") (pin "2") (pintype "passive")))
    (net (code "86") (name "5VSB") (class "Default")
      (node (ref "C68") (pin "2") (pinfunction "2_2") (pintype "passive"))
      (node (ref "C69") (pin "2") (pinfunction "2_2") (pintype "passive"))
      (node (ref "P5") (pin "5") (pinfunction "5_5") (pintype "passive"))
      (node (ref "U11") (pin "3") (pinfunction "VIN_3") (pintype "power_in"))
    )
    (net (code "87") (name "D3V3") (class "Default")
      (node (ref "C46") (pin "2") (pinfunction "2_2") (pintype "passive"))
      (node (ref "C47") (pin "2") (pinfunction "2_2") (pintype "passive"))
      (node (ref "L5") (pin "2") (pinfunction "2_2") (pintype "passive"))
      (node (ref "P3") (pin "1") (pinfunction "1_1") (pintype "passive"))
      (node (ref "P5") (pin "2") (pinfunction "2_2") (pintype "passive"))
      (node (ref "P7") (pin "1") (pinfunction "1_1") (pintype "passive"))
      (node (ref "U6") (pin "15") (pinfunction "VDDTX_15") (pintype "power_in"))
      (node (ref "U6") (pin "19") (pinfunction "VDDRX_19") (pintype "power_in"))
      (node (ref "U6") (pin "20") (pinfunction "VDDPLL_20") (pintype "power_in"))
      (node (ref "U6") (pin "25") (pinfunction "VDDOSC_25") (pintype "power_in"))
      (node (ref "U6") (pin "28") (pinfunction "VDD_28") (pintype "power_in"))
      (node (ref "U7") (pin "16") (pinfunction "VCC_16") (pintype "passive"))
      (node (ref "U7") (pin "6") (pinfunction "G1_6") (pintype "passive"))
    )
    (net (code "88") (name "ECVDD") (class "Default")
      (node (ref "C70") (pin "2") (pinfunction "2_2") (pintype "passive"))
      (node (ref "C71") (pin "2") (pinfunction "2_2") (pintype "passive"))
      (node (ref "C72") (pin "2") (pinfunction "2_2") (pintype "passive"))
      (node (ref "C73") (pin "2") (pinfunction "2_2") (pintype "passive"))
      (node (ref "C74") (pin "2") (pinfunction "2_2") (pintype "passive"))
      (node (ref "D3") (pin "1") (pinfunction "A_1") (pintype "passive"))
      (node (ref "L8") (pin "2") (pinfunction "2_2") (pintype "passive"))
      (node (ref "PD3") (pin "1") (pinfunction "VDD_1") (pintype "passive"))
      (node (ref "U11") (pin "2") (pinfunction "VOUT_2") (pintype "power_in"))
      (node (ref "U8") (pin "19") (pinfunction "VDD_4_19") (pintype "passive"))
      (node (ref "U8") (pin "32") (pinfunction "VDD_1_32") (pintype "passive"))
      (node (ref "U8") (pin "48") (pinfunction "VDD_2_48") (pintype "passive"))
      (node (ref "U8") (pin "64") (pinfunction "VDD_3_64") (pintype "passive"))
    )
    (net (code "89") (name "GND") (class "Default")
      (node (ref "BT1") (pin "2") (pinfunction "-_2") (pintype "passive"))
      (node (ref "C45") (pin "2") (pinfunction "2_2") (pintype "passive"))
      (node (ref "C46") (pin "1") (pinfunction "1_1") (pintype "passive"))
      (node (ref "C47") (pin "1") (pinfunction "1_1") (pintype "passive"))
      (node (ref "C48") (pin "2") (pinfunction "2_2") (pintype "passive"))
      (node (ref "C49") (pin "2") (pinfunction "2_2") (pintype "passive"))
      (node (ref "C50") (pin "1") (pinfunction "1_1") (pintype "passive"))
      (node (ref "C51") (pin "1") (pinfunction "1_1") (pintype "passive"))
      (node (ref "C52") (pin "2") (pinfunction "2_2") (pintype "passive"))
      (node (ref "C53") (pin "1") (pinfunction "1_1") (pintype "passive"))
      (node (ref "C55") (pin "2") (pinfunction "2_2") (pintype "passive"))
      (node (ref "C56") (pin "1") (pinfunction "1_1") (pintype "passive"))
      (node (ref "C57") (pin "2") (pinfunction "2_2") (pintype "passive"))
      (node (ref "C58") (pin "1") (pinfunction "1_1") (pintype "passive"))
      (node (ref "C60") (pin "2") (pinfunction "2_2") (pintype "passive"))
      (node (ref "C61") (pin "1") (pinfunction "1_1") (pintype "passive"))
      (node (ref "C62") (pin "2") (pinfunction "2_2") (pintype "passive"))
      (node (ref "C63") (pin "1") (pinfunction "1_1") (pintype "passive"))
      (node (ref "C64") (pin "2") (pinfunction "2_2") (pintype "passive"))
      (node (ref "C65") (pin "2") (pinfunction "2_2") (pintype "passive"))
      (node (ref "C66") (pin "2") (pinfunction "2_2") (pintype "passive"))
      (node (ref "C67") (pin "2") (pinfunction "2_2") (pintype "passive"))
      (node (ref "C68") (pin "1") (pinfunction "1_1") (pintype "passive"))
      (node (ref "C69") (pin "1") (pinfunction "1_1") (pintype "passive"))
      (node (ref "C70") (pin "1") (pinfunction "1_1") (pintype "passive"))
      (node (ref "C71") (pin "1") (pinfunction "1_1") (pintype "passive"))
      (node (ref "C72") (pin "1") (pinfunction "1_1") (pintype "passive"))
      (node (ref "C73") (pin "1") (pinfunction "1_1") (pintype "passive"))
      (node (ref "C74") (pin "1") (pinfunction "1_1") (pintype "passive"))
      (node (ref "C75") (pin "1") (pinfunction "1_1") (pintype "passive"))
      (node (ref "P3") (pin "11") (pinfunction "11_11") (pintype "passive"))
      (node (ref "P4") (pin "10") (pinfunction "LED1-_10") (pintype "passive"))
      (node (ref "P4") (pin "11") (pinfunction "LED2-_11") (pintype "passive"))
      (node (ref "P4") (pin "S") (pinfunction "GND_S") (pintype "passive"))
      (node (ref "P5") (pin "6") (pinfunction "6_6") (pintype "passive"))
      (node (ref "P6") (pin "4") (pinfunction "4_4") (pintype "passive"))
      (node (ref "P6") (pin "5") (pinfunction "5_5") (pintype "passive"))
      (node (ref "P6") (pin "6") (pinfunction "6_6") (pintype "passive"))
      (node (ref "P6") (pin "7") (pinfunction "7_7") (pintype "passive"))
      (node (ref "P6") (pin "8") (pinfunction "8_8") (pintype "passive"))
      (node (ref "P8") (pin "1") (pinfunction "1_1") (pintype "passive"))
      (node (ref "PD3") (pin "6") (pinfunction "GND_6") (pintype "passive"))
      (node (ref "R44") (pin "2") (pinfunction "2_2") (pintype "passive"))
      (node (ref "R45") (pin "2") (pinfunction "2_2") (pintype "passive"))
      (node (ref "R46") (pin "1") (pinfunction "1_1") (pintype "passive"))
      (node (ref "R48") (pin "2") (pinfunction "2_2") (pintype "passive"))
      (node (ref "R49") (pin "2") (pinfunction "2_2") (pintype "passive"))
      (node (ref "R50") (pin "1") (pinfunction "1_1") (pintype "passive"))
      (node (ref "R53") (pin "2") (pinfunction "2_2") (pintype "passive"))
      (node (ref "R54") (pin "2") (pinfunction "2_2") (pintype "passive"))
      (node (ref "S2") (pin "1") (pinfunction "1_1") (pintype "passive"))
      (node (ref "U10") (pin "1") (pinfunction "GND_1") (pintype "power_in"))
      (node (ref "U11") (pin "1") (pinfunction "GND_1") (pintype "power_in"))
      (node (ref "U6") (pin "11") (pinfunction "VSSRX_11") (pintype "power_in"))
      (node (ref "U6") (pin "18") (pinfunction "VSSTX_18") (pintype "power_in"))
      (node (ref "U6") (pin "2") (pinfunction "VSS_2") (pintype "power_in"))
      (node (ref "U6") (pin "21") (pinfunction "VSSPLL_21") (pintype "power_in"))
      (node (ref "U6") (pin "22") (pinfunction "VSSOSC_22") (pintype "power_in"))
      (node (ref "U7") (pin "5") (pinfunction "~{G2B}_5") (pintype "passive"))
      (node (ref "U7") (pin "8") (pinfunction "GND_8") (pintype "passive"))
      (node (ref "U8") (pin "12") (pinfunction "VSSA_12") (pintype "passive"))
      (node (ref "U8") (pin "18") (pinfunction "VSS_4_18") (pintype "passive"))
      (node (ref "U8") (pin "31") (pinfunction "VSS_1_31") (pintype "passive"))
      (node (ref "U8") (pin "47") (pinfunction "VSS_2_47") (pintype "passive"))
      (node (ref "U8") (pin "60") (pinfunction "BOOT0_60") (pintype "passive"))
      (node (ref "U8") (pin "63") (pinfunction "VSS_3_63") (pintype "passive"))
      (node (ref "U9") (pin "1") (pinfunction "GND_1") (pintype "power_in"))
    )
    (net (code "90") (name "Net-(BT1-+)") (class "Default")
      (node (ref "BT1") (pin "1") (pinfunction "+_1") (pintype "passive"))
      (node (ref "D4") (pin "1") (pinfunction "A_1") (pintype "passive"))
    )
    (net (code "91") (name "Net-(C50-Pad2)") (class "Default")
      (node (ref "C50") (pin "2") (pinfunction "2_2") (pintype "passive"))
      (node (ref "L5") (pin "1") (pinfunction "1_1") (pintype "passive"))
      (node (ref "R40") (pin "2") (pinfunction "2_2") (pintype "passive"))
      (node (ref "R41") (pin "2") (pinfunction "2_2") (pintype "passive"))
    )
    (net (code "92") (name "Net-(C51-Pad2)") (class "Default")
      (node (ref "C51") (pin "2") (pinfunction "2_2") (pintype "passive"))
      (node (ref "R42") (pin "2") (pinfunction "2_2") (pintype "passive"))
      (node (ref "R43") (pin "2") (pinfunction "2_2") (pintype "passive"))
    )
    (net (code "93") (name "Net-(D2-K)") (class "Default")
      (node (ref "D2") (pin "2") (pinfunction "K_2") (pintype "passive"))
      (node (ref "R48") (pin "1") (pinfunction "1_1") (pintype "passive"))
    )
    (net (code "94") (name "Net-(U6-LEDA)") (class "Default")
      (node (ref "R38") (pin "2") (pinfunction "2_2") (pintype "passive"))
      (node (ref "U6") (pin "27") (pinfunction "LEDA_27") (pintype "output"))
    )
    (net (code "95") (name "Net-(U6-LEDB)") (class "Default")
      (node (ref "R39") (pin "2") (pinfunction "2_2") (pintype "passive"))
      (node (ref "U6") (pin "26") (pinfunction "LEDB_26") (pintype "output"))
    )
    (net (code "96") (name "Net-(U6-RBIAS)") (class "Default")
      (node (ref "R44") (pin "1") (pinfunction "1_1") (pintype "passive"))
      (node (ref "U6") (pin "14") (pinfunction "RBIAS_14") (pintype "power_in"))
    )
    (net (code "97") (name "Net-(U6-VCAP)") (class "Default")
      (node (ref "C45") (pin "1") (pinfunction "1_1") (pintype "passive"))
      (node (ref "U6") (pin "1") (pinfunction "VCAP_1") (pintype "output"))
    )
    (net (code "98") (name "Net-(U9-BST)") (class "Default")
      (node (ref "C54") (pin "2") (pinfunction "2_2") (pintype "passive"))
      (node (ref "U9") (pin "6") (pinfunction "BST_6") (pintype "power_in"))
    )
    (net (code "99") (name "Net-(U9-FB)") (class "Default")
      (node (ref "R46") (pin "2") (pinfunction "2_2") (pintype "passive"))
      (node (ref "R47") (pin "1") (pinfunction "1_1") (pintype "passive"))
      (node (ref "U9") (pin "4") (pinfunction "FB_4") (pintype "power_in"))
    )
    (net (code "100") (name "Net-(U9-SW)") (class "Default")
      (node (ref "C54") (pin "1") (pinfunction "1_1") (pintype "passive"))
      (node (ref "L6") (pin "1") (pinfunction "1_1") (pintype "passive"))
      (node (ref "U9") (pin "2") (pinfunction "SW_2") (pintype "power_in"))
    )
    (net (code "101") (name "Net-(U10-BST)") (class "Default")
      (node (ref "C59") (pin "2") (pinfunction "2_2") (pintype "passive"))
      (node (ref "U10") (pin "6") (pinfunction "BST_6") (pintype "power_in"))
    )
    (net (code "102") (name "Net-(U10-FB)") (class "Default")
      (node (ref "R50") (pin "2") (pinfunction "2_2") (pintype "passive"))
      (node (ref "R51") (pin "1") (pinfunction "1_1") (pintype "passive"))
      (node (ref "U10") (pin "4") (pinfunction "FB_4") (pintype "power_in"))
    )
    (net (code "103") (name "Net-(U10-SW)") (class "Default")
      (node (ref "C59") (pin "1") (pinfunction "1_1") (pintype "passive"))
      (node (ref "L7") (pin "1") (pinfunction "1_1") (pintype "passive"))
      (node (ref "U10") (pin "2") (pinfunction "SW_2") (pintype "power_in"))
    )
    (net (code "104") (name "VBUS") (class "Default")
      (node (ref "C52") (pin "1") (pinfunction "1_1") (pintype "passive"))
      (node (ref "C53") (pin "2") (pinfunction "2_2") (pintype "passive"))
      (node (ref "F1") (pin "2") (pinfunction "2_2") (pintype "passive"))
      (node (ref "P6") (pin "1") (pinfunction "1_1") (pintype "passive"))
    )
    (net (code "105") (name "unconnected-(P4-N.C.-Pad4)") (class "Default")
      (node (ref "P4") (pin "4") (pinfunction "N.C._4") (pintype "passive"))
    )
    (net (code "106") (name "unconnected-(P4-N.C.-Pad5)") (class "Default")
      (node (ref "P4") (pin "5") (pinfunction "N.C._5") (pintype "passive"))
    )
    (net (code "107") (name "unconnected-(P4-N.C.-Pad7)") (class "Default")
      (node (ref "P4") (pin "7") (pinfunction "N.C._7") (pintype "passive"))
    )
    (net (code "108") (name "unconnected-(P4-N.C.-Pad8)") (class "Default")
      (node (ref "P4") (pin "8") (pinfunction "N.C._8") (pintype "passive"))
    )
    (net (code "109") (name "unconnected-(U6-CLKOUT-Pad3)") (class "Default")
      (node (ref "U6") (pin "3") (pinfunction "CLKOUT_3") (pintype "output+no_connect"))
    )
    (net (code "110") (name "unconnected-(U8B-PC13-TAMPER-RTC-Pad2)") (class "Default")
      (node (ref "U8") (pin "2") (pinfunction "PC13-TAMPER-RTC_2") (pintype "passive+no_connect"))
    )
  )
)
